# pishield.net
KiCad netlist of a schematic drawn in EAGLE
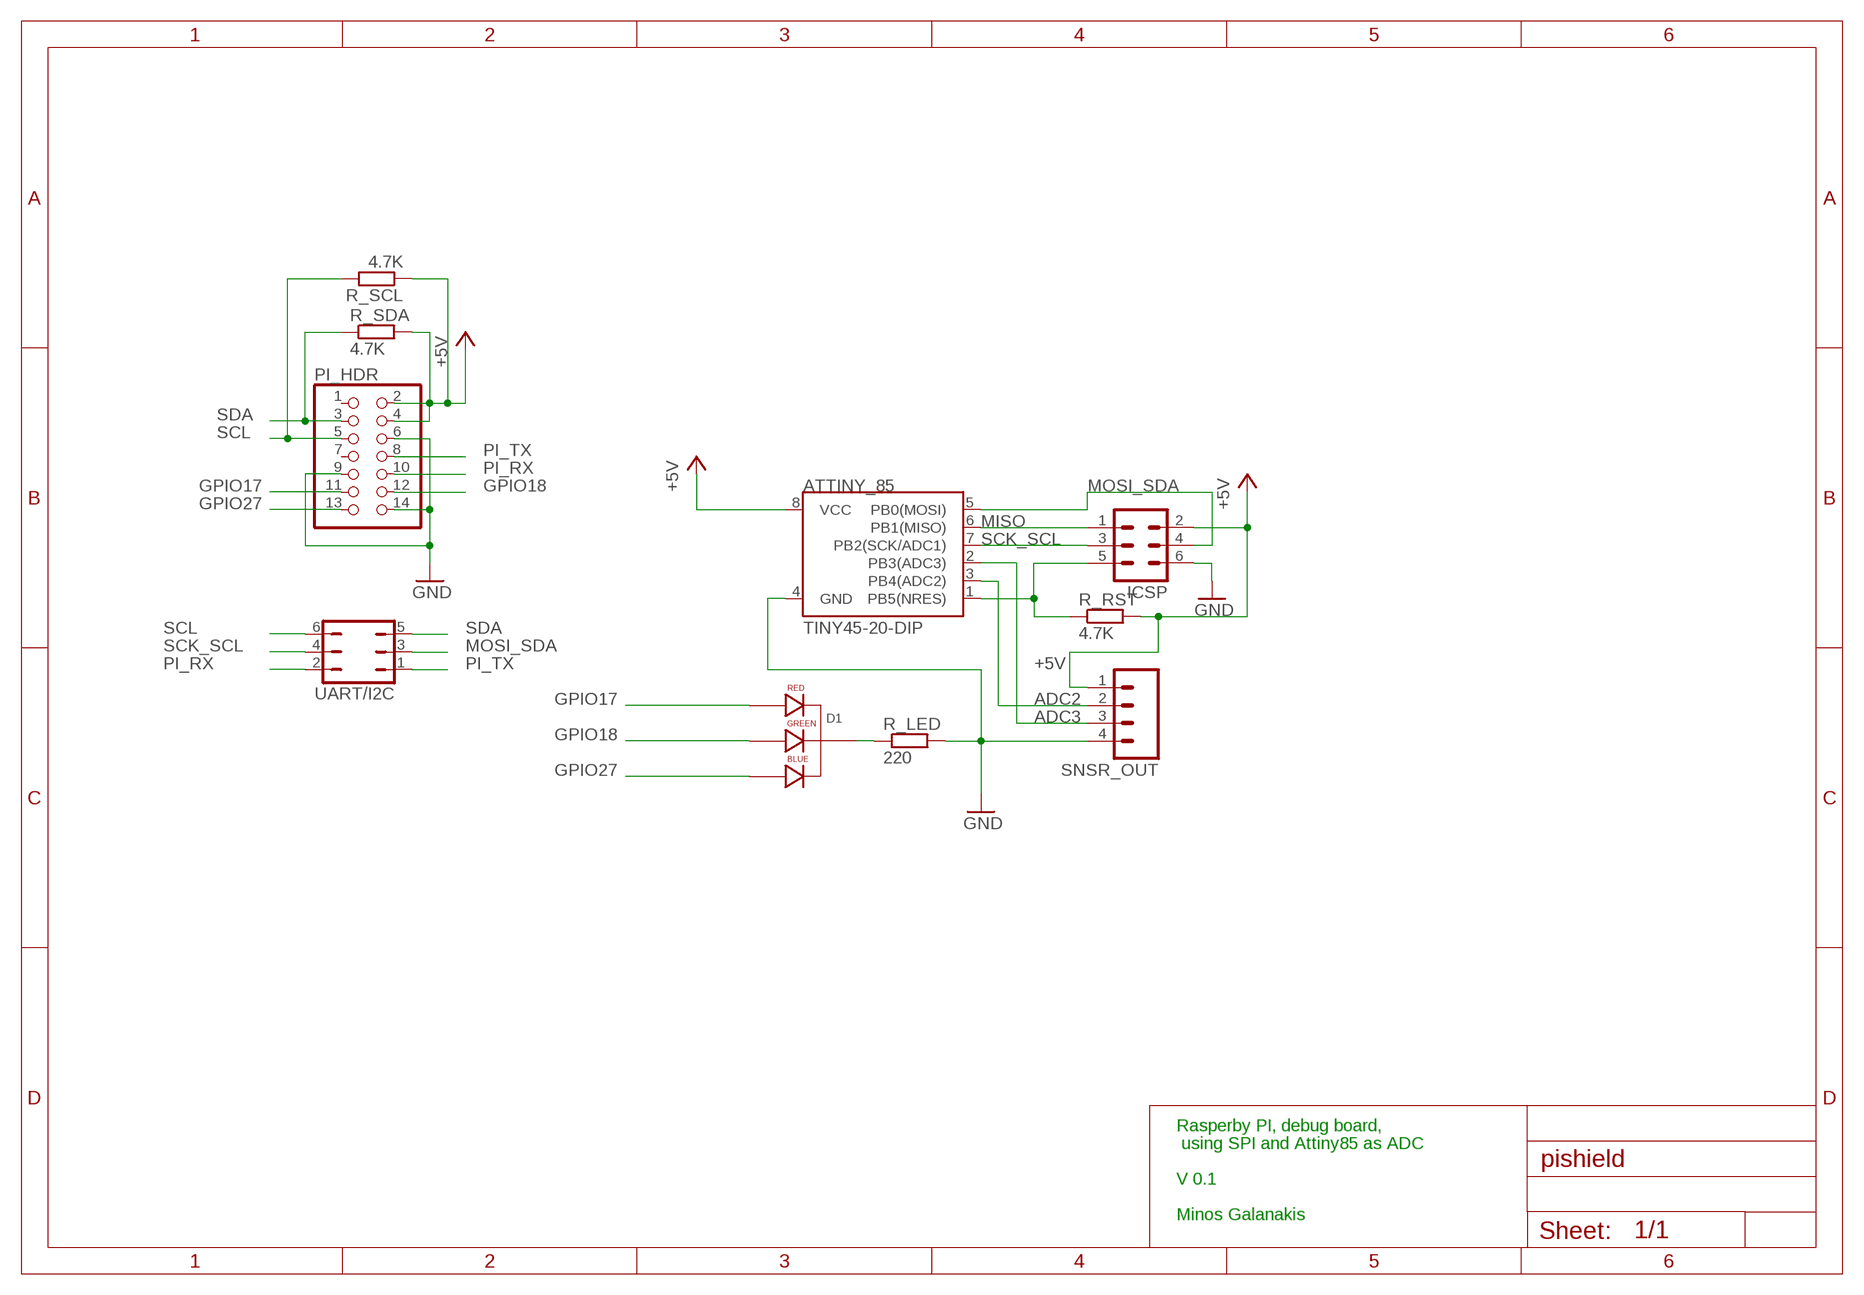
[diagram p0: schematic, sheet 1]

(export (version "E")
  (design (tool "Eeschema 10.0.6"))
  (components
    (comp (ref "ATTINY_85")
      (value "TINY45-20-DIP")
      (footprint "eagle-import:DIP08")
      (libsource (lib "eagle-import") (part "ATTINY45TINY45-20-DIP"))
    )
    (comp (ref "D1")
      (value "LED-RGB-CC-THRUCLEAR")
      (footprint "eagle-import:LED-RGB-THRU")
      (libsource (lib "eagle-import") (part "LED-RGB-CC-THRUCLEAR"))
    )
    (comp (ref "ICSP")
      (value "MA03-2")
      (footprint "eagle-import:MA03-2")
      (libsource (lib "eagle-import") (part "MA03-2"))
    )
    (comp (ref "PI_HDR")
      (value "PINHD-2X7")
      (footprint "eagle-import:2X07")
      (libsource (lib "eagle-import") (part "PINHD-2X7"))
    )
    (comp (ref "R_LED")
      (value "220")
      (footprint "eagle-import:0204_7")
      (libsource (lib "eagle-import") (part "R-EU_0204/7"))
    )
    (comp (ref "R_RST")
      (value "4.7K")
      (footprint "eagle-import:0204_7")
      (libsource (lib "eagle-import") (part "R-EU_0204/7"))
    )
    (comp (ref "R_SCL")
      (value "4.7K")
      (footprint "eagle-import:0204_7")
      (libsource (lib "eagle-import") (part "R-EU_0204/7"))
    )
    (comp (ref "R_SDA")
      (value "4.7K")
      (footprint "eagle-import:0204_7")
      (libsource (lib "eagle-import") (part "R-EU_0204/7"))
    )
    (comp (ref "SNSR_OUT")
      (value "M04LONGPADS")
      (footprint "eagle-import:1X04_LONGPADS")
      (libsource (lib "eagle-import") (part "M04LONGPADS"))
    )
    (comp (ref "UART/I2C")
      (value "JP3Q")
      (footprint "eagle-import:JP3Q")
      (libsource (lib "eagle-import") (part "JP3Q"))
    )
  )
  (nets
    (net (code "1") (name "+5V") (class "Default")
      (node (ref "ATTINY_85") (pin "8") (pinfunction "VCC_8") (pintype "bidirectional"))
      (node (ref "ICSP") (pin "2") (pinfunction "2_2") (pintype "passive"))
      (node (ref "PI_HDR") (pin "2") (pinfunction "2_2") (pintype "passive"))
      (node (ref "PI_HDR") (pin "4") (pinfunction "4_4") (pintype "passive"))
      (node (ref "R_RST") (pin "2") (pinfunction "2_2") (pintype "passive"))
      (node (ref "R_SCL") (pin "1") (pinfunction "1_1") (pintype "passive"))
      (node (ref "R_SDA") (pin "2") (pinfunction "2_2") (pintype "passive"))
      (node (ref "SNSR_OUT") (pin "1") (pinfunction "1_1") (pintype "passive"))
    )
    (net (code "2") (name "/ADC2") (class "Default")
      (node (ref "ATTINY_85") (pin "3") (pinfunction "PB4(ADC2)_3") (pintype "bidirectional"))
      (node (ref "SNSR_OUT") (pin "2") (pinfunction "2_2") (pintype "passive"))
    )
    (net (code "3") (name "/ADC3") (class "Default")
      (node (ref "ATTINY_85") (pin "2") (pinfunction "PB3(ADC3)_2") (pintype "bidirectional"))
      (node (ref "SNSR_OUT") (pin "3") (pinfunction "3_3") (pintype "passive"))
    )
    (net (code "4") (name "/GPIO17") (class "Default")
      (node (ref "D1") (pin "1") (pinfunction "RED_CATHODE_1") (pintype "bidirectional"))
      (node (ref "PI_HDR") (pin "11") (pinfunction "11_11") (pintype "passive"))
    )
    (net (code "5") (name "/GPIO18") (class "Default")
      (node (ref "D1") (pin "3") (pinfunction "GREEN_CATHODE_3") (pintype "bidirectional"))
      (node (ref "PI_HDR") (pin "12") (pinfunction "12_12") (pintype "passive"))
    )
    (net (code "6") (name "/GPIO27") (class "Default")
      (node (ref "D1") (pin "4") (pinfunction "BLUE_CATHODE_4") (pintype "bidirectional"))
      (node (ref "PI_HDR") (pin "13") (pinfunction "13_13") (pintype "passive"))
    )
    (net (code "7") (name "/MISO") (class "Default")
      (node (ref "ATTINY_85") (pin "6") (pinfunction "PB1(MISO)_6") (pintype "bidirectional"))
      (node (ref "ICSP") (pin "1") (pinfunction "1_1") (pintype "passive"))
    )
    (net (code "8") (name "/MOSI_SDA") (class "Default")
      (node (ref "ATTINY_85") (pin "5") (pinfunction "PB0(MOSI)_5") (pintype "bidirectional"))
      (node (ref "ICSP") (pin "4") (pinfunction "4_4") (pintype "passive"))
      (node (ref "UART/I2C") (pin "3") (pinfunction "3_3") (pintype "passive"))
    )
    (net (code "9") (name "/PI_RX") (class "Default")
      (node (ref "PI_HDR") (pin "10") (pinfunction "10_10") (pintype "passive"))
      (node (ref "UART/I2C") (pin "2") (pinfunction "2_2") (pintype "passive"))
    )
    (net (code "10") (name "/PI_TX") (class "Default")
      (node (ref "PI_HDR") (pin "8") (pinfunction "8_8") (pintype "passive"))
      (node (ref "UART/I2C") (pin "1") (pinfunction "1_1") (pintype "passive"))
    )
    (net (code "11") (name "/SCK_SCL") (class "Default")
      (node (ref "ATTINY_85") (pin "7") (pinfunction "PB2(SCK/ADC1)_7") (pintype "bidirectional"))
      (node (ref "ICSP") (pin "3") (pinfunction "3_3") (pintype "passive"))
      (node (ref "UART/I2C") (pin "4") (pinfunction "4_4") (pintype "passive"))
    )
    (net (code "12") (name "/SCL") (class "Default")
      (node (ref "PI_HDR") (pin "5") (pinfunction "5_5") (pintype "passive"))
      (node (ref "R_SCL") (pin "2") (pinfunction "2_2") (pintype "passive"))
      (node (ref "UART/I2C") (pin "6") (pinfunction "6_6") (pintype "passive"))
    )
    (net (code "13") (name "/SDA") (class "Default")
      (node (ref "PI_HDR") (pin "3") (pinfunction "3_3") (pintype "passive"))
      (node (ref "R_SDA") (pin "1") (pinfunction "1_1") (pintype "passive"))
      (node (ref "UART/I2C") (pin "5") (pinfunction "5_5") (pintype "passive"))
    )
    (net (code "14") (name "GND") (class "Default")
      (node (ref "ATTINY_85") (pin "4") (pinfunction "GND_4") (pintype "bidirectional"))
      (node (ref "ICSP") (pin "6") (pinfunction "6_6") (pintype "passive"))
      (node (ref "PI_HDR") (pin "14") (pinfunction "14_14") (pintype "passive"))
      (node (ref "PI_HDR") (pin "6") (pinfunction "6_6") (pintype "passive"))
      (node (ref "PI_HDR") (pin "9") (pinfunction "9_9") (pintype "passive"))
      (node (ref "R_LED") (pin "2") (pinfunction "2_2") (pintype "passive"))
      (node (ref "SNSR_OUT") (pin "4") (pinfunction "4_4") (pintype "passive"))
    )
    (net (code "15") (name "Net-(ATTINY_85-PB5(NRES))") (class "Default")
      (node (ref "ATTINY_85") (pin "1") (pinfunction "PB5(NRES)_1") (pintype "bidirectional"))
      (node (ref "ICSP") (pin "5") (pinfunction "5_5") (pintype "passive"))
      (node (ref "R_RST") (pin "1") (pinfunction "1_1") (pintype "passive"))
    )
    (net (code "16") (name "Net-(D1-CATHODE)") (class "Default")
      (node (ref "D1") (pin "2") (pinfunction "CATHODE_2") (pintype "bidirectional"))
      (node (ref "R_LED") (pin "1") (pinfunction "1_1") (pintype "passive"))
    )
    (net (code "17") (name "unconnected-(PI_HDR-Pad1)") (class "Default")
      (node (ref "PI_HDR") (pin "1") (pinfunction "1_1") (pintype "passive"))
    )
    (net (code "18") (name "unconnected-(PI_HDR-Pad7)") (class "Default")
      (node (ref "PI_HDR") (pin "7") (pinfunction "7_7") (pintype "passive"))
    )
  )
)
